# comparator.net
KiCad netlist of a schematic drawn in Altium Designer
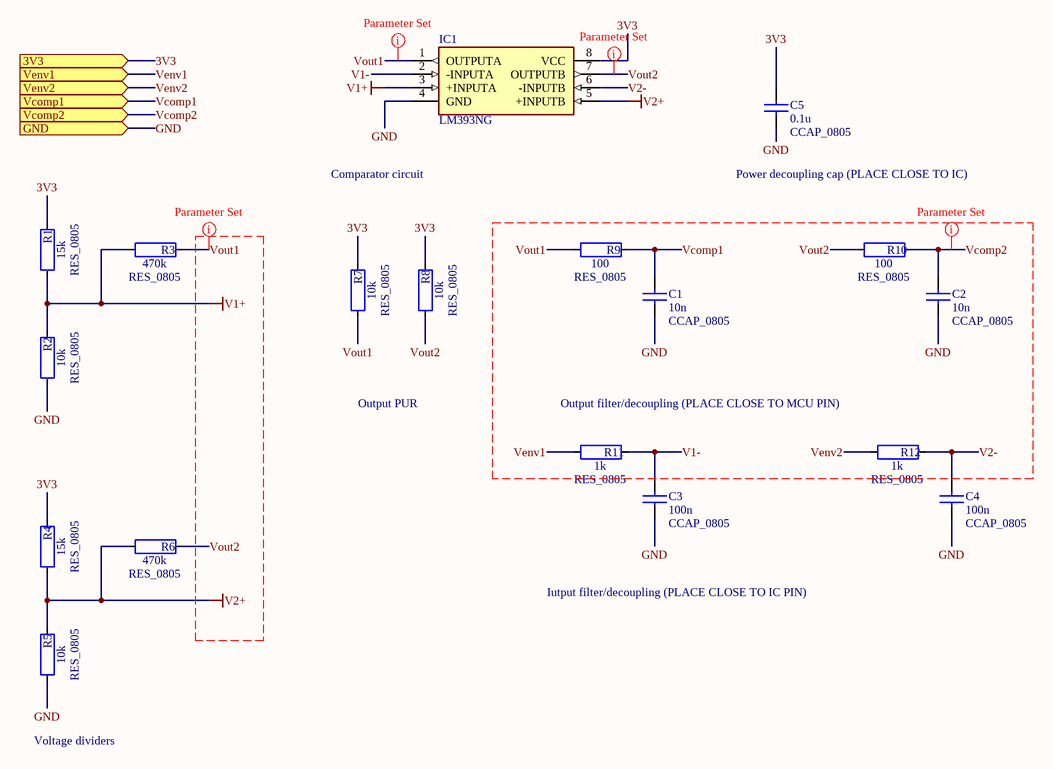
[diagram p0: comparator.SchDoc]

(export (version "E")
  (design (tool "Eeschema 10.0.6"))
  (components
    (comp (ref "C1")
      (value "CCAP_0805")
      (footprint "C0805")
      (description "Generic 0805 cramic capacitor")
      (fields (field (name "ALTIUM_VALUE") "10n"))
      (libsource (lib "UGs@UoA") (part "CCAP0805"))
    )
    (comp (ref "C2")
      (value "CCAP_0805")
      (footprint "C0805")
      (description "Generic 0805 cramic capacitor")
      (fields (field (name "ALTIUM_VALUE") "10n"))
      (libsource (lib "UGs@UoA") (part "CCAP0805"))
    )
    (comp (ref "C3")
      (value "CCAP_0805")
      (footprint "C0805")
      (description "Generic 0805 cramic capacitor")
      (fields (field (name "ALTIUM_VALUE") "100n"))
      (libsource (lib "UGs@UoA") (part "CCAP0805"))
    )
    (comp (ref "C4")
      (value "CCAP_0805")
      (footprint "C0805")
      (description "Generic 0805 cramic capacitor")
      (fields (field (name "ALTIUM_VALUE") "100n"))
      (libsource (lib "UGs@UoA") (part "CCAP0805"))
    )
    (comp (ref "C5")
      (value "CCAP_0805")
      (footprint "C0805")
      (description "Generic 0805 cramic capacitor")
      (fields (field (name "ALTIUM_VALUE") "0.1u"))
      (libsource (lib "UGs@UoA") (part "CCAP0805"))
    )
    (comp (ref "IC1")
      (value "LM393NG")
      (footprint "SamacSys:DIP794W56P254L959H533Q8B")
      (description "Integrated Circuit")
      (fields (field (name "MOUSER PART NUMBER") "863-LM393NG"))
      (libsource (lib "SamacSys") (part "LM393NG"))
    )
    (comp (ref "R1")
      (value "RES_0805")
      (footprint "R0805")
      (description "Generic 0805 resistor")
      (fields (field (name "ALTIUM_VALUE") "15k"))
      (libsource (lib "") (part "RES0805_1"))
    )
    (comp (ref "R2")
      (value "RES_0805")
      (footprint "R0805")
      (description "Generic 0805 resistor")
      (fields (field (name "ALTIUM_VALUE") "10k"))
      (libsource (lib "") (part "RES0805_1"))
    )
    (comp (ref "R3")
      (value "RES_0805")
      (footprint "R0805")
      (description "Generic 0805 resistor")
      (fields (field (name "ALTIUM_VALUE") "470k"))
      (libsource (lib "UGs@UoA") (part "RES0805"))
    )
    (comp (ref "R4")
      (value "RES_0805")
      (footprint "R0805")
      (description "Generic 0805 resistor")
      (fields (field (name "ALTIUM_VALUE") "15k"))
      (libsource (lib "") (part "RES0805_1"))
    )
    (comp (ref "R5")
      (value "RES_0805")
      (footprint "R0805")
      (description "Generic 0805 resistor")
      (fields (field (name "ALTIUM_VALUE") "10k"))
      (libsource (lib "") (part "RES0805_1"))
    )
    (comp (ref "R6")
      (value "RES_0805")
      (footprint "R0805")
      (description "Generic 0805 resistor")
      (fields (field (name "ALTIUM_VALUE") "470k"))
      (libsource (lib "UGs@UoA") (part "RES0805"))
    )
    (comp (ref "R7")
      (value "RES_0805")
      (footprint "R0805")
      (description "Generic 0805 resistor")
      (fields (field (name "ALTIUM_VALUE") "10k"))
      (libsource (lib "") (part "RES0805_1"))
    )
    (comp (ref "R8")
      (value "RES_0805")
      (footprint "R0805")
      (description "Generic 0805 resistor")
      (fields (field (name "ALTIUM_VALUE") "10k"))
      (libsource (lib "") (part "RES0805_1"))
    )
    (comp (ref "R9")
      (value "RES_0805")
      (footprint "R0805")
      (description "Generic 0805 resistor")
      (fields (field (name "ALTIUM_VALUE") "100"))
      (libsource (lib "UGs@UoA") (part "RES0805"))
    )
    (comp (ref "R10")
      (value "RES_0805")
      (footprint "R0805")
      (description "Generic 0805 resistor")
      (fields (field (name "ALTIUM_VALUE") "100"))
      (libsource (lib "UGs@UoA") (part "RES0805"))
    )
    (comp (ref "R11")
      (value "RES_0805")
      (footprint "R0805")
      (description "Generic 0805 resistor")
      (fields (field (name "ALTIUM_VALUE") "1k"))
      (libsource (lib "UGs@UoA") (part "RES0805"))
    )
    (comp (ref "R12")
      (value "RES_0805")
      (footprint "R0805")
      (description "Generic 0805 resistor")
      (fields (field (name "ALTIUM_VALUE") "1k"))
      (libsource (lib "UGs@UoA") (part "RES0805"))
    )
  )
  (nets
    (net (code "1") (name "/3V3") (class "Default")
      (node (ref "C5") (pin "2") (pinfunction "2_2") (pintype "passive"))
      (node (ref "IC1") (pin "8") (pinfunction "VCC_8") (pintype "power_in"))
      (node (ref "R1") (pin "2") (pinfunction "2_2") (pintype "passive"))
      (node (ref "R4") (pin "2") (pinfunction "2_2") (pintype "passive"))
      (node (ref "R7") (pin "2") (pinfunction "2_2") (pintype "passive"))
      (node (ref "R8") (pin "2") (pinfunction "2_2") (pintype "passive"))
    )
    (net (code "2") (name "/GND") (class "Default")
      (node (ref "C1") (pin "1") (pinfunction "1_1") (pintype "passive"))
      (node (ref "C2") (pin "1") (pinfunction "1_1") (pintype "passive"))
      (node (ref "C3") (pin "1") (pinfunction "1_1") (pintype "passive"))
      (node (ref "C4") (pin "1") (pinfunction "1_1") (pintype "passive"))
      (node (ref "C5") (pin "1") (pinfunction "1_1") (pintype "passive"))
      (node (ref "IC1") (pin "4") (pinfunction "GND_4") (pintype "power_in"))
      (node (ref "R2") (pin "1") (pinfunction "1_1") (pintype "passive"))
      (node (ref "R5") (pin "1") (pinfunction "1_1") (pintype "passive"))
    )
    (net (code "3") (name "/V1-") (class "Default")
      (node (ref "C3") (pin "2") (pinfunction "2_2") (pintype "passive"))
      (node (ref "IC1") (pin "2") (pinfunction "-INPUTA_2") (pintype "input"))
      (node (ref "R11") (pin "2") (pinfunction "2_2") (pintype "passive"))
    )
    (net (code "4") (name "/V2-") (class "Default")
      (node (ref "C4") (pin "2") (pinfunction "2_2") (pintype "passive"))
      (node (ref "IC1") (pin "6") (pinfunction "-INPUTB_6") (pintype "input"))
      (node (ref "R12") (pin "2") (pinfunction "2_2") (pintype "passive"))
    )
    (net (code "5") (name "/Vcomp1") (class "Default")
      (node (ref "C1") (pin "2") (pinfunction "2_2") (pintype "passive"))
      (node (ref "R9") (pin "2") (pinfunction "2_2") (pintype "passive"))
    )
    (net (code "6") (name "/Vcomp2") (class "Default")
      (node (ref "C2") (pin "2") (pinfunction "2_2") (pintype "passive"))
      (node (ref "R10") (pin "2") (pinfunction "2_2") (pintype "passive"))
    )
    (net (code "7") (name "/Venv1") (class "Default")
      (node (ref "R11") (pin "1") (pinfunction "1_1") (pintype "passive"))
    )
    (net (code "8") (name "/Venv2") (class "Default")
      (node (ref "R12") (pin "1") (pinfunction "1_1") (pintype "passive"))
    )
    (net (code "9") (name "/Vout1") (class "Default")
      (node (ref "IC1") (pin "1") (pinfunction "OUTPUTA_1") (pintype "output"))
      (node (ref "R3") (pin "2") (pinfunction "2_2") (pintype "passive"))
      (node (ref "R7") (pin "1") (pinfunction "1_1") (pintype "passive"))
      (node (ref "R9") (pin "1") (pinfunction "1_1") (pintype "passive"))
    )
    (net (code "10") (name "/Vout2") (class "Default")
      (node (ref "IC1") (pin "7") (pinfunction "OUTPUTB_7") (pintype "output"))
      (node (ref "R10") (pin "1") (pinfunction "1_1") (pintype "passive"))
      (node (ref "R6") (pin "2") (pinfunction "2_2") (pintype "passive"))
      (node (ref "R8") (pin "1") (pinfunction "1_1") (pintype "passive"))
    )
    (net (code "11") (name "V1+") (class "Default")
      (node (ref "IC1") (pin "3") (pinfunction "+INPUTA_3") (pintype "input"))
      (node (ref "R1") (pin "1") (pinfunction "1_1") (pintype "passive"))
      (node (ref "R2") (pin "2") (pinfunction "2_2") (pintype "passive"))
      (node (ref "R3") (pin "1") (pinfunction "1_1") (pintype "passive"))
    )
    (net (code "12") (name "V2+") (class "Default")
      (node (ref "IC1") (pin "5") (pinfunction "+INPUTB_5") (pintype "input"))
      (node (ref "R4") (pin "1") (pinfunction "1_1") (pintype "passive"))
      (node (ref "R5") (pin "2") (pinfunction "2_2") (pintype "passive"))
      (node (ref "R6") (pin "1") (pinfunction "1_1") (pintype "passive"))
    )
  )
)
